# openLRSngTX.net
KiCad netlist of a schematic drawn in EAGLE
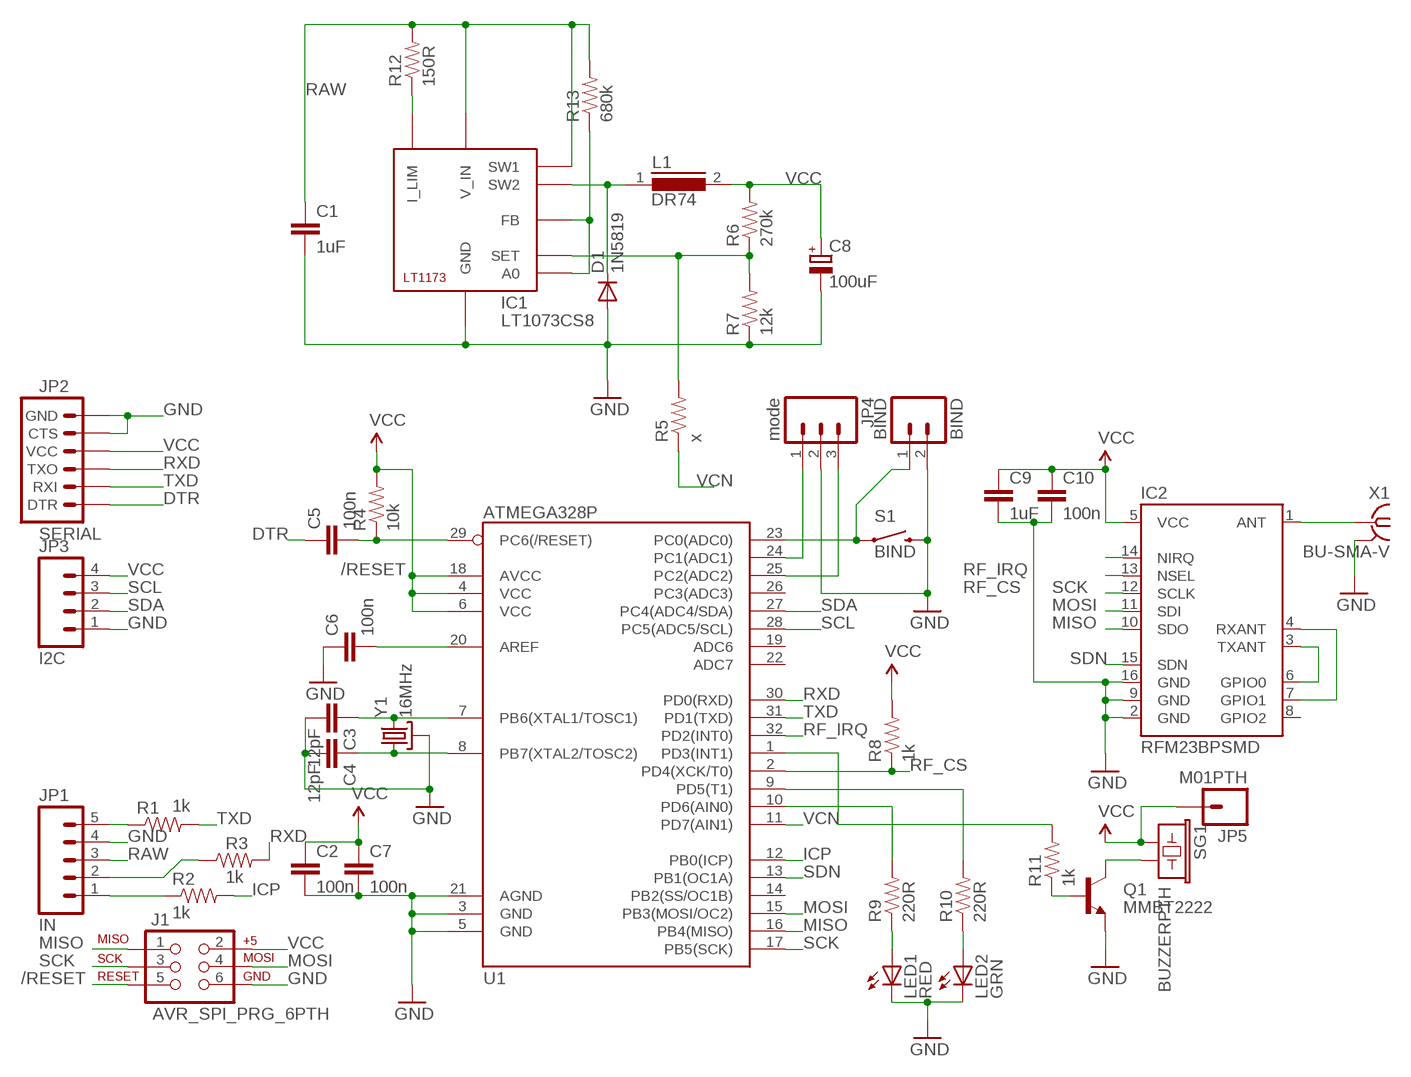
[diagram p0: schematic, sheet 1]

(export (version "E")
  (design (tool "Eeschema 10.0.6"))
  (components
    (comp (ref "BIND")
      (value "BIND")
      (footprint "eagle-import:1X02")
      (libsource (lib "eagle-import") (part "M02PTH"))
    )
    (comp (ref "C1")
      (value "1uF")
      (footprint "eagle-import:0805")
      (libsource (lib "eagle-import") (part "CAP0805"))
    )
    (comp (ref "C2")
      (value "100n")
      (footprint "eagle-import:0805")
      (libsource (lib "eagle-import") (part "CAP0805"))
    )
    (comp (ref "C3")
      (value "12pF")
      (footprint "eagle-import:0805")
      (libsource (lib "eagle-import") (part "CAP0805"))
    )
    (comp (ref "C4")
      (value "12pF")
      (footprint "eagle-import:0805")
      (libsource (lib "eagle-import") (part "CAP0805"))
    )
    (comp (ref "C5")
      (value "100n")
      (footprint "eagle-import:0805")
      (libsource (lib "eagle-import") (part "CAP0805"))
    )
    (comp (ref "C6")
      (value "100n")
      (footprint "eagle-import:0805")
      (libsource (lib "eagle-import") (part "CAP0805"))
    )
    (comp (ref "C7")
      (value "100n")
      (footprint "eagle-import:0805")
      (libsource (lib "eagle-import") (part "CAP0805"))
    )
    (comp (ref "C8")
      (value "100uF")
      (footprint "eagle-import:D_7343-31W")
      (libsource (lib "eagle-import") (part "CPOL-EUD/7343-31W"))
    )
    (comp (ref "C9")
      (value "1uF")
      (footprint "eagle-import:0805")
      (libsource (lib "eagle-import") (part "CAP0805"))
    )
    (comp (ref "C10")
      (value "100n")
      (footprint "eagle-import:0805")
      (libsource (lib "eagle-import") (part "CAP0805"))
    )
    (comp (ref "D1")
      (value "1N5819")
      (footprint "eagle-import:DO214AC")
      (libsource (lib "eagle-import") (part "DIODE-DO214AC"))
    )
    (comp (ref "IC1")
      (value "LT1073CS8")
      (footprint "eagle-import:SOIC8")
      (libsource (lib "eagle-import") (part "LT1173CS8"))
    )
    (comp (ref "IC2")
      (value "RFM23BPSMD")
      (footprint "eagle-import:RFM23BP-S2")
      (libsource (lib "eagle-import") (part "RFM23BPSMD"))
    )
    (comp (ref "J1")
      (value "AVR_SPI_PRG_6PTH")
      (footprint "eagle-import:2X3")
      (libsource (lib "eagle-import") (part "AVR_SPI_PRG_6PTH"))
    )
    (comp (ref "JP1")
      (value "IN")
      (footprint "eagle-import:1X05")
      (libsource (lib "eagle-import") (part "M05PTH"))
    )
    (comp (ref "JP2")
      (value "SERIAL")
      (footprint "eagle-import:1X06")
      (libsource (lib "eagle-import") (part "ARDUINO_SERIAL_PROGRAMPTH"))
    )
    (comp (ref "JP3")
      (value "I2C")
      (footprint "eagle-import:1X04")
      (libsource (lib "eagle-import") (part "M04PTH"))
    )
    (comp (ref "JP4")
      (value "mode")
      (footprint "eagle-import:1X03")
      (libsource (lib "eagle-import") (part "M03PTH"))
    )
    (comp (ref "JP5")
      (value "M01PTH")
      (footprint "eagle-import:1X01")
      (libsource (lib "eagle-import") (part "M01PTH"))
    )
    (comp (ref "L1")
      (value "DR74")
      (footprint "eagle-import:DR74")
      (libsource (lib "eagle-import") (part "DR74"))
    )
    (comp (ref "LED1")
      (value "RED")
      (footprint "eagle-import:LED3MM")
      (libsource (lib "eagle-import") (part "LED3MM"))
    )
    (comp (ref "LED2")
      (value "GRN")
      (footprint "eagle-import:LED3MM")
      (libsource (lib "eagle-import") (part "LED3MM"))
    )
    (comp (ref "Q1")
      (value "MMBT2222")
      (footprint "eagle-import:SOT23-3")
      (libsource (lib "eagle-import") (part "TRANSISTOR_NPNSOT23-3"))
    )
    (comp (ref "R1")
      (value "1k")
      (footprint "eagle-import:0805")
      (libsource (lib "eagle-import") (part "RESISTOR0805-RES"))
    )
    (comp (ref "R2")
      (value "1k")
      (footprint "eagle-import:0805")
      (libsource (lib "eagle-import") (part "RESISTOR0805-RES"))
    )
    (comp (ref "R3")
      (value "1k")
      (footprint "eagle-import:0805")
      (libsource (lib "eagle-import") (part "RESISTOR0805-RES"))
    )
    (comp (ref "R4")
      (value "10k")
      (footprint "eagle-import:0805")
      (libsource (lib "eagle-import") (part "RESISTOR0805-RES"))
    )
    (comp (ref "R5")
      (value "x")
      (footprint "eagle-import:0805")
      (libsource (lib "eagle-import") (part "RESISTOR0805-RES"))
    )
    (comp (ref "R6")
      (value "270k")
      (footprint "eagle-import:0805")
      (libsource (lib "eagle-import") (part "RESISTOR0805-RES"))
    )
    (comp (ref "R7")
      (value "12k")
      (footprint "eagle-import:0805")
      (libsource (lib "eagle-import") (part "RESISTOR0805-RES"))
    )
    (comp (ref "R8")
      (value "1k")
      (footprint "eagle-import:0805")
      (libsource (lib "eagle-import") (part "RESISTOR0805-RES"))
    )
    (comp (ref "R9")
      (value "220R")
      (footprint "eagle-import:0805")
      (libsource (lib "eagle-import") (part "RESISTOR0805-RES"))
    )
    (comp (ref "R10")
      (value "220R")
      (footprint "eagle-import:0805")
      (libsource (lib "eagle-import") (part "RESISTOR0805-RES"))
    )
    (comp (ref "R11")
      (value "1k")
      (footprint "eagle-import:0805")
      (libsource (lib "eagle-import") (part "RESISTOR0805-RES"))
    )
    (comp (ref "R12")
      (value "150R")
      (footprint "eagle-import:0805")
      (libsource (lib "eagle-import") (part "RESISTOR0805-RES"))
    )
    (comp (ref "R13")
      (value "680k")
      (footprint "eagle-import:0805")
      (libsource (lib "eagle-import") (part "RESISTOR0805-RES"))
    )
    (comp (ref "S1")
      (value "BIND")
      (footprint "eagle-import:TACTILE_SWITCH_TALL")
      (libsource (lib "eagle-import") (part "SWITCH-MOMENTARY-2"))
    )
    (comp (ref "SG1")
      (value "BUZZERPTH")
      (footprint "eagle-import:BUZZER-12MM")
      (libsource (lib "eagle-import") (part "BUZZERPTH"))
    )
    (comp (ref "U1")
      (value "ATMEGA328P")
      (footprint "eagle-import:TQFP32-08")
      (libsource (lib "eagle-import") (part "ATMEGA328_SMT"))
    )
    (comp (ref "X1")
      (value "BU-SMA-V")
      (footprint "eagle-import:BU-SMA-V")
      (libsource (lib "eagle-import") (part "BU-SMA-V"))
    )
    (comp (ref "Y1")
      (value "16MHz")
      (footprint "eagle-import:CRYSTAL-SMD-5X3")
      (libsource (lib "eagle-import") (part "CRYSTAL3.2X2.5"))
    )
  )
  (nets
    (net (code "1") (name "/DTR") (class "Default")
      (node (ref "C5") (pin "1") (pinfunction "1_1") (pintype "passive"))
      (node (ref "JP2") (pin "1") (pinfunction "DTR_1") (pintype "passive"))
    )
    (net (code "2") (name "/ICP") (class "Default")
      (node (ref "R2") (pin "2") (pinfunction "2_2") (pintype "passive"))
      (node (ref "U1") (pin "12") (pinfunction "PB0(ICP)_12") (pintype "bidirectional"))
    )
    (net (code "3") (name "/MISO") (class "Default")
      (node (ref "IC2") (pin "10") (pinfunction "SDO_10") (pintype "output"))
      (node (ref "J1") (pin "1") (pinfunction "1_1") (pintype "passive"))
      (node (ref "U1") (pin "16") (pinfunction "PB4(MISO)_16") (pintype "bidirectional"))
    )
    (net (code "4") (name "/MOSI") (class "Default")
      (node (ref "IC2") (pin "11") (pinfunction "SDI_11") (pintype "input"))
      (node (ref "J1") (pin "4") (pinfunction "4_4") (pintype "passive"))
      (node (ref "U1") (pin "15") (pinfunction "PB3(MOSI/OC2)_15") (pintype "bidirectional"))
    )
    (net (code "5") (name "/RAW") (class "Default")
      (node (ref "C1") (pin "1") (pinfunction "1_1") (pintype "passive"))
      (node (ref "IC1") (pin "2") (pinfunction "V_IN_2") (pintype "passive"))
      (node (ref "IC1") (pin "3") (pinfunction "SW1_3") (pintype "passive"))
      (node (ref "JP1") (pin "3") (pinfunction "3_3") (pintype "passive"))
      (node (ref "R12") (pin "2") (pinfunction "2_2") (pintype "passive"))
      (node (ref "R13") (pin "2") (pinfunction "2_2") (pintype "passive"))
    )
    (net (code "6") (name "/RF_CS") (class "Default")
      (node (ref "IC2") (pin "13") (pinfunction "NSEL_13") (pintype "input"))
      (node (ref "R8") (pin "1") (pinfunction "1_1") (pintype "passive"))
      (node (ref "U1") (pin "2") (pinfunction "PD4(XCK/T0)_2") (pintype "bidirectional"))
    )
    (net (code "7") (name "/RF_IRQ") (class "Default")
      (node (ref "IC2") (pin "14") (pinfunction "NIRQ_14") (pintype "output"))
      (node (ref "U1") (pin "32") (pinfunction "PD2(INT0)_32") (pintype "bidirectional"))
    )
    (net (code "8") (name "/RXD") (class "Default")
      (node (ref "JP2") (pin "3") (pinfunction "TXO_3") (pintype "passive"))
      (node (ref "R3") (pin "2") (pinfunction "2_2") (pintype "passive"))
      (node (ref "U1") (pin "30") (pinfunction "PD0(RXD)_30") (pintype "bidirectional"))
    )
    (net (code "9") (name "/SCK") (class "Default")
      (node (ref "IC2") (pin "12") (pinfunction "SCLK_12") (pintype "input"))
      (node (ref "J1") (pin "3") (pinfunction "3_3") (pintype "passive"))
      (node (ref "U1") (pin "17") (pinfunction "PB5(SCK)_17") (pintype "bidirectional"))
    )
    (net (code "10") (name "/SCL") (class "Default")
      (node (ref "JP3") (pin "3") (pinfunction "3_3") (pintype "passive"))
      (node (ref "U1") (pin "28") (pinfunction "PC5(ADC5/SCL)_28") (pintype "bidirectional"))
    )
    (net (code "11") (name "/SDA") (class "Default")
      (node (ref "JP3") (pin "2") (pinfunction "2_2") (pintype "passive"))
      (node (ref "U1") (pin "27") (pinfunction "PC4(ADC4/SDA)_27") (pintype "bidirectional"))
    )
    (net (code "12") (name "/SDN") (class "Default")
      (node (ref "IC2") (pin "15") (pinfunction "SDN_15") (pintype "input"))
      (node (ref "U1") (pin "13") (pinfunction "PB1(OC1A)_13") (pintype "bidirectional"))
    )
    (net (code "13") (name "/TXD") (class "Default")
      (node (ref "JP2") (pin "2") (pinfunction "RXI_2") (pintype "passive"))
      (node (ref "R1") (pin "2") (pinfunction "2_2") (pintype "passive"))
      (node (ref "U1") (pin "31") (pinfunction "PD1(TXD)_31") (pintype "bidirectional"))
    )
    (net (code "14") (name "/VCN") (class "Default")
      (node (ref "R5") (pin "1") (pinfunction "1_1") (pintype "passive"))
      (node (ref "U1") (pin "11") (pinfunction "PD7(AIN1)_11") (pintype "bidirectional"))
    )
    (net (code "15") (name "/{slash}RESET") (class "Default")
      (node (ref "C5") (pin "2") (pinfunction "2_2") (pintype "passive"))
      (node (ref "J1") (pin "5") (pinfunction "5_5") (pintype "passive"))
      (node (ref "R4") (pin "1") (pinfunction "1_1") (pintype "passive"))
      (node (ref "U1") (pin "29") (pinfunction "PC6(/RESET)_29") (pintype "bidirectional"))
    )
    (net (code "16") (name "GND") (class "Default")
      (node (ref "BIND") (pin "2") (pinfunction "2_2") (pintype "passive"))
      (node (ref "C1") (pin "2") (pinfunction "2_2") (pintype "passive"))
      (node (ref "C10") (pin "2") (pinfunction "2_2") (pintype "passive"))
      (node (ref "C2") (pin "2") (pinfunction "2_2") (pintype "passive"))
      (node (ref "C3") (pin "2") (pinfunction "2_2") (pintype "passive"))
      (node (ref "C4") (pin "2") (pinfunction "2_2") (pintype "passive"))
      (node (ref "C6") (pin "1") (pinfunction "1_1") (pintype "passive"))
      (node (ref "C7") (pin "2") (pinfunction "2_2") (pintype "passive"))
      (node (ref "C8") (pin "-") (pinfunction "-_-") (pintype "passive"))
      (node (ref "C9") (pin "2") (pinfunction "2_2") (pintype "passive"))
      (node (ref "D1") (pin "A") (pinfunction "A_A") (pintype "passive"))
      (node (ref "IC1") (pin "5") (pinfunction "GND_5") (pintype "power_in"))
      (node (ref "IC2") (pin "16") (pinfunction "GND_16") (pintype "power_in"))
      (node (ref "IC2") (pin "2") (pinfunction "GND_2") (pintype "power_in"))
      (node (ref "IC2") (pin "9") (pinfunction "GND_9") (pintype "power_in"))
      (node (ref "J1") (pin "6") (pinfunction "6_6") (pintype "passive"))
      (node (ref "JP1") (pin "4") (pinfunction "4_4") (pintype "passive"))
      (node (ref "JP2") (pin "5") (pinfunction "CTS_5") (pintype "passive"))
      (node (ref "JP2") (pin "6") (pinfunction "GND_6") (pintype "passive"))
      (node (ref "JP3") (pin "1") (pinfunction "1_1") (pintype "passive"))
      (node (ref "JP4") (pin "2") (pinfunction "2_2") (pintype "passive"))
      (node (ref "LED1") (pin "K") (pinfunction "C_K") (pintype "passive"))
      (node (ref "LED2") (pin "K") (pinfunction "C_K") (pintype "passive"))
      (node (ref "Q1") (pin "2") (pinfunction "E_2") (pintype "passive"))
      (node (ref "R7") (pin "1") (pinfunction "1_1") (pintype "passive"))
      (node (ref "S1") (pin "B2") (pinfunction "2_B2") (pintype "passive"))
      (node (ref "U1") (pin "21") (pinfunction "AGND_21") (pintype "bidirectional"))
      (node (ref "U1") (pin "3") (pinfunction "GND_3") (pintype "bidirectional"))
      (node (ref "U1") (pin "5") (pinfunction "GND_5") (pintype "bidirectional"))
      (node (ref "X1") (pin "2") (pinfunction "2_2") (pintype "passive"))
      (node (ref "X1") (pin "3") (pinfunction "2_3") (pintype "passive"))
      (node (ref "X1") (pin "4") (pinfunction "2_4") (pintype "passive"))
      (node (ref "X1") (pin "5") (pinfunction "2_5") (pintype "passive"))
      (node (ref "Y1") (pin "2") (pinfunction "GND_2") (pintype "power_in"))
      (node (ref "Y1") (pin "4") (pinfunction "GND_4") (pintype "power_in"))
    )
    (net (code "17") (name "Net-(IC1-A0)") (class "Default")
      (node (ref "IC1") (pin "6") (pinfunction "A0_6") (pintype "passive"))
      (node (ref "IC1") (pin "8") (pinfunction "FB_8") (pintype "passive"))
      (node (ref "R13") (pin "1") (pinfunction "1_1") (pintype "passive"))
    )
    (net (code "18") (name "Net-(IC1-I_LIM)") (class "Default")
      (node (ref "IC1") (pin "1") (pinfunction "I_LIM_1") (pintype "passive"))
      (node (ref "R12") (pin "1") (pinfunction "1_1") (pintype "passive"))
    )
    (net (code "19") (name "Net-(IC1-SET)") (class "Default")
      (node (ref "IC1") (pin "7") (pinfunction "SET_7") (pintype "passive"))
      (node (ref "R5") (pin "2") (pinfunction "2_2") (pintype "passive"))
      (node (ref "R6") (pin "1") (pinfunction "1_1") (pintype "passive"))
      (node (ref "R7") (pin "2") (pinfunction "2_2") (pintype "passive"))
    )
    (net (code "20") (name "Net-(IC1-SW2)") (class "Default")
      (node (ref "D1") (pin "C") (pinfunction "C_C") (pintype "passive"))
      (node (ref "IC1") (pin "4") (pinfunction "SW2_4") (pintype "passive"))
      (node (ref "L1") (pin "1") (pinfunction "1_1") (pintype "passive"))
    )
    (net (code "21") (name "Net-(IC2-ANT)") (class "Default")
      (node (ref "IC2") (pin "1") (pinfunction "ANT_1") (pintype "bidirectional"))
      (node (ref "X1") (pin "1") (pinfunction "1_1") (pintype "passive"))
    )
    (net (code "22") (name "Net-(IC2-GPIO0)") (class "Default")
      (node (ref "IC2") (pin "3") (pinfunction "TXANT_3") (pintype "input"))
      (node (ref "IC2") (pin "6") (pinfunction "GPIO0_6") (pintype "bidirectional"))
    )
    (net (code "23") (name "Net-(IC2-GPIO1)") (class "Default")
      (node (ref "IC2") (pin "4") (pinfunction "RXANT_4") (pintype "input"))
      (node (ref "IC2") (pin "7") (pinfunction "GPIO1_7") (pintype "bidirectional"))
    )
    (net (code "24") (name "Net-(JP1-Pad1)") (class "Default")
      (node (ref "JP1") (pin "1") (pinfunction "1_1") (pintype "passive"))
      (node (ref "R2") (pin "1") (pinfunction "1_1") (pintype "passive"))
    )
    (net (code "25") (name "Net-(JP1-Pad2)") (class "Default")
      (node (ref "JP1") (pin "2") (pinfunction "2_2") (pintype "passive"))
      (node (ref "R3") (pin "1") (pinfunction "1_1") (pintype "passive"))
    )
    (net (code "26") (name "Net-(JP1-Pad5)") (class "Default")
      (node (ref "JP1") (pin "5") (pinfunction "5_5") (pintype "passive"))
      (node (ref "R1") (pin "1") (pinfunction "1_1") (pintype "passive"))
    )
    (net (code "27") (name "Net-(LED1-PadA)") (class "Default")
      (node (ref "LED1") (pin "A") (pinfunction "A_A") (pintype "passive"))
      (node (ref "R9") (pin "1") (pinfunction "1_1") (pintype "passive"))
    )
    (net (code "28") (name "Net-(LED2-PadA)") (class "Default")
      (node (ref "LED2") (pin "A") (pinfunction "A_A") (pintype "passive"))
      (node (ref "R10") (pin "1") (pinfunction "1_1") (pintype "passive"))
    )
    (net (code "29") (name "Net-(Q1-B)") (class "Default")
      (node (ref "Q1") (pin "1") (pinfunction "B_1") (pintype "passive"))
      (node (ref "R11") (pin "1") (pinfunction "1_1") (pintype "passive"))
    )
    (net (code "30") (name "Net-(Q1-C)") (class "Default")
      (node (ref "Q1") (pin "3") (pinfunction "C_3") (pintype "passive"))
      (node (ref "SG1") (pin "-") (pinfunction "2_-") (pintype "passive"))
    )
    (net (code "31") (name "Net-(S1-1)") (class "Default")
      (node (ref "BIND") (pin "1") (pinfunction "1_1") (pintype "passive"))
      (node (ref "S1") (pin "A2") (pinfunction "1_A2") (pintype "passive"))
      (node (ref "U1") (pin "23") (pinfunction "PC0(ADC0)_23") (pintype "bidirectional"))
    )
    (net (code "32") (name "Net-(U1-AREF)") (class "Default")
      (node (ref "C6") (pin "2") (pinfunction "2_2") (pintype "passive"))
      (node (ref "U1") (pin "20") (pinfunction "AREF_20") (pintype "bidirectional"))
    )
    (net (code "33") (name "Net-(U1-PB6(XTAL1{slash}TOSC1))") (class "Default")
      (node (ref "C3") (pin "1") (pinfunction "1_1") (pintype "passive"))
      (node (ref "U1") (pin "7") (pinfunction "PB6(XTAL1/TOSC1)_7") (pintype "bidirectional"))
      (node (ref "Y1") (pin "3") (pinfunction "2_3") (pintype "passive"))
    )
    (net (code "34") (name "Net-(U1-PB7(XTAL2{slash}TOSC2))") (class "Default")
      (node (ref "C4") (pin "1") (pinfunction "1_1") (pintype "passive"))
      (node (ref "U1") (pin "8") (pinfunction "PB7(XTAL2/TOSC2)_8") (pintype "bidirectional"))
      (node (ref "Y1") (pin "1") (pinfunction "1_1") (pintype "passive"))
    )
    (net (code "35") (name "Net-(U1-PC1(ADC1))") (class "Default")
      (node (ref "JP4") (pin "1") (pinfunction "1_1") (pintype "passive"))
      (node (ref "U1") (pin "24") (pinfunction "PC1(ADC1)_24") (pintype "bidirectional"))
    )
    (net (code "36") (name "Net-(U1-PC2(ADC2))") (class "Default")
      (node (ref "JP4") (pin "3") (pinfunction "3_3") (pintype "passive"))
      (node (ref "U1") (pin "25") (pinfunction "PC2(ADC2)_25") (pintype "bidirectional"))
    )
    (net (code "37") (name "Net-(U1-PD3(INT1))") (class "Default")
      (node (ref "R11") (pin "2") (pinfunction "2_2") (pintype "passive"))
      (node (ref "U1") (pin "1") (pinfunction "PD3(INT1)_1") (pintype "bidirectional"))
    )
    (net (code "38") (name "Net-(U1-PD5(T1))") (class "Default")
      (node (ref "R10") (pin "2") (pinfunction "2_2") (pintype "passive"))
      (node (ref "U1") (pin "9") (pinfunction "PD5(T1)_9") (pintype "bidirectional"))
    )
    (net (code "39") (name "Net-(U1-PD6(AIN0))") (class "Default")
      (node (ref "R9") (pin "2") (pinfunction "2_2") (pintype "passive"))
      (node (ref "U1") (pin "10") (pinfunction "PD6(AIN0)_10") (pintype "bidirectional"))
    )
    (net (code "40") (name "VCC") (class "Default")
      (node (ref "C10") (pin "1") (pinfunction "1_1") (pintype "passive"))
      (node (ref "C2") (pin "1") (pinfunction "1_1") (pintype "passive"))
      (node (ref "C7") (pin "1") (pinfunction "1_1") (pintype "passive"))
      (node (ref "C8") (pin "+") (pinfunction "+_+") (pintype "passive"))
      (node (ref "C9") (pin "1") (pinfunction "1_1") (pintype "passive"))
      (node (ref "IC2") (pin "5") (pinfunction "VCC_5") (pintype "bidirectional"))
      (node (ref "J1") (pin "2") (pinfunction "2_2") (pintype "passive"))
      (node (ref "JP2") (pin "4") (pinfunction "VCC_4") (pintype "passive"))
      (node (ref "JP3") (pin "4") (pinfunction "4_4") (pintype "passive"))
      (node (ref "JP5") (pin "1") (pinfunction "1_1") (pintype "passive"))
      (node (ref "L1") (pin "2") (pinfunction "2_2") (pintype "passive"))
      (node (ref "R4") (pin "2") (pinfunction "2_2") (pintype "passive"))
      (node (ref "R6") (pin "2") (pinfunction "2_2") (pintype "passive"))
      (node (ref "R8") (pin "2") (pinfunction "2_2") (pintype "passive"))
      (node (ref "SG1") (pin "+") (pinfunction "1_+") (pintype "passive"))
      (node (ref "U1") (pin "18") (pinfunction "AVCC_18") (pintype "bidirectional"))
      (node (ref "U1") (pin "4") (pinfunction "VCC_4") (pintype "bidirectional"))
      (node (ref "U1") (pin "6") (pinfunction "VCC_6") (pintype "bidirectional"))
    )
    (net (code "41") (name "unconnected-(IC2-GPIO2-Pad8)") (class "Default")
      (node (ref "IC2") (pin "8") (pinfunction "GPIO2_8") (pintype "bidirectional"))
    )
    (net (code "42") (name "unconnected-(U1-ADC6-Pad19)") (class "Default")
      (node (ref "U1") (pin "19") (pinfunction "ADC6_19") (pintype "bidirectional"))
    )
    (net (code "43") (name "unconnected-(U1-ADC7-Pad22)") (class "Default")
      (node (ref "U1") (pin "22") (pinfunction "ADC7_22") (pintype "bidirectional"))
    )
    (net (code "44") (name "unconnected-(U1-PB2(SS{slash}OC1B)-Pad14)") (class "Default")
      (node (ref "U1") (pin "14") (pinfunction "PB2(SS/OC1B)_14") (pintype "bidirectional"))
    )
    (net (code "45") (name "unconnected-(U1-PC3(ADC3)-Pad26)") (class "Default")
      (node (ref "U1") (pin "26") (pinfunction "PC3(ADC3)_26") (pintype "bidirectional"))
    )
  )
)
